# Sheet1.net
KiCad netlist of a schematic drawn in Altium Designer
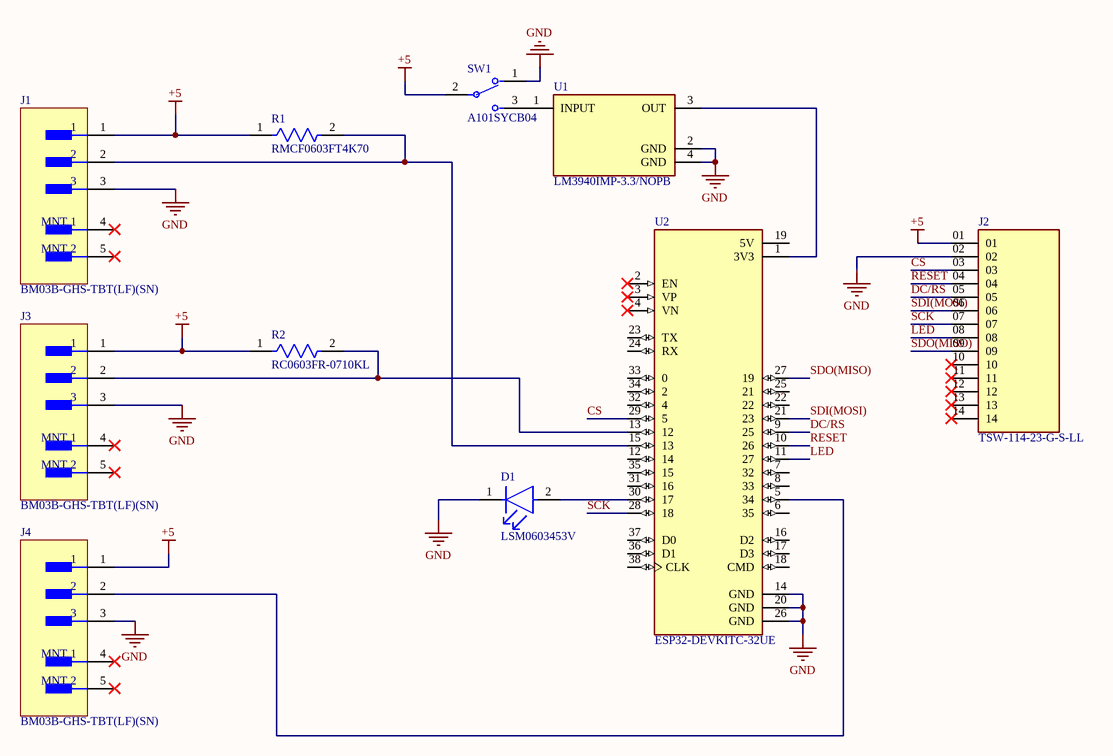
[diagram p0: Sheet1.SchDoc]

(export (version "E")
  (design (tool "Eeschema 10.0.6"))
  (components
    (comp (ref "D1")
      (value "LSM0603453V")
      (footprint "FP-LSM0603453V-MFG")
      (description "LSM0603453V LED SM 0603 3V -/1000/-mcd Green")
      (libsource (lib "Altium Content Vault") (part "8706943c75ba83719d021d2fdc84c58"))
    )
    (comp (ref "J1")
      (value "BM03B-GHS-TBT(LF)(SN)")
      (footprint "FP-BM03B-GHS-TBT_LF_SN-MFG")
      (description "CONN HEADER SMD 3POS 1.25MM")
      (libsource (lib "Altium Content Vault") (part "BM03B-GHS-TBT_LF_SN"))
    )
    (comp (ref "J2")
      (value "TSW-114-23-G-S-LL")
      (footprint "PcbLib1:SAMTEC_TSW-114-23-G-S-LL")
      (libsource (lib "Schlib1") (part "TSW-114-23-G-S-LL"))
    )
    (comp (ref "J3")
      (value "BM03B-GHS-TBT(LF)(SN)")
      (footprint "FP-BM03B-GHS-TBT_LF_SN-MFG")
      (description "CONN HEADER SMD 3POS 1.25MM")
      (libsource (lib "Altium Content Vault") (part "BM03B-GHS-TBT_LF_SN"))
    )
    (comp (ref "J4")
      (value "BM03B-GHS-TBT(LF)(SN)")
      (footprint "FP-BM03B-GHS-TBT_LF_SN-MFG")
      (description "CONN HEADER SMD 3POS 1.25MM")
      (libsource (lib "Altium Content Vault") (part "BM03B-GHS-TBT_LF_SN"))
    )
    (comp (ref "R1")
      (value "RMCF0603FT4K70")
      (footprint "FP-RMCF0603-IPC_B")
      (description "4.7kΩ ±1% 0.1W 0603 Thick Film Chip Resistor AEC-Q200 compliant")
      (fields (field (name "TOLERANCE") "1%"))
      (libsource (lib "Altium Content Vault") (part "1029c3af85768c4190bb7ad29bc67b5"))
    )
    (comp (ref "R2")
      (value "RC0603FR-0710KL")
      (footprint "FP-RC0603-0_55-IPC_C")
      (description "RES 10K OHM 1% 1/10W 0603")
      (fields (field (name "TOLERANCE") "1%"))
      (libsource (lib "Altium Content Vault") (part "1029c3af85768c4190bb7ad29bc67b5"))
    )
    (comp (ref "SW1")
      (value "A101SYCB04")
      (footprint "FP-A101SYCB04-MFG")
      (description "SWITCH TOGGLE SPDT 0.4VA 20V")
      (libsource (lib "Altium Content Vault") (part "52c419afdc2a387c7d548259a9aeefb"))
    )
    (comp (ref "U1")
      (value "LM3940IMP-3.3/NOPB")
      (footprint "FP-DCY0004A-MFG")
      (description "IC REG LINEAR 3.3V 1A SOT223-4")
      (libsource (lib "Altium Content Vault") (part "ef78896361455d16e3252a05c23564e"))
    )
    (comp (ref "U2")
      (value "ESP32-DEVKITC-32UE")
      (footprint "PcbLib1:ESPRESSIF_ESP32-DEVKITC-32UE")
      (fields (field (name "MF") "Espressif Systems"))
      (libsource (lib "Schlib1") (part "ESP32-DEVKITC-32UE"))
    )
  )
  (nets
    (net (code "1") (name "+5") (class "Default")
      (node (ref "J1") (pin "1") (pinfunction "1_1") (pintype "passive"))
      (node (ref "J2") (pin "01") (pinfunction "01_01") (pintype "passive"))
      (node (ref "J3") (pin "1") (pinfunction "1_1") (pintype "passive"))
      (node (ref "J4") (pin "1") (pinfunction "1_1") (pintype "passive"))
      (node (ref "R1") (pin "1") (pinfunction "1_1") (pintype "passive"))
      (node (ref "R2") (pin "1") (pinfunction "1_1") (pintype "passive"))
      (node (ref "SW1") (pin "2") (pinfunction "2_2") (pintype "passive"))
    )
    (net (code "2") (name "/CS") (class "Default")
      (node (ref "J2") (pin "03") (pinfunction "03_03") (pintype "passive"))
      (node (ref "U2") (pin "29") (pinfunction "5_29") (pintype "bidirectional"))
    )
    (net (code "3") (name "/DC{slash}RS") (class "Default")
      (node (ref "J2") (pin "05") (pinfunction "05_05") (pintype "passive"))
      (node (ref "U2") (pin "9") (pinfunction "25_9") (pintype "bidirectional"))
    )
    (net (code "4") (name "/LED") (class "Default")
      (node (ref "J2") (pin "08") (pinfunction "08_08") (pintype "passive"))
      (node (ref "U2") (pin "11") (pinfunction "27_11") (pintype "bidirectional"))
    )
    (net (code "5") (name "/RESET") (class "Default")
      (node (ref "J2") (pin "04") (pinfunction "04_04") (pintype "passive"))
      (node (ref "U2") (pin "10") (pinfunction "26_10") (pintype "bidirectional"))
    )
    (net (code "6") (name "/SCK") (class "Default")
      (node (ref "J2") (pin "07") (pinfunction "07_07") (pintype "passive"))
      (node (ref "U2") (pin "28") (pinfunction "18_28") (pintype "bidirectional"))
    )
    (net (code "7") (name "/SDI(MOSI)") (class "Default")
      (node (ref "J2") (pin "06") (pinfunction "06_06") (pintype "passive"))
      (node (ref "U2") (pin "21") (pinfunction "23_21") (pintype "bidirectional"))
    )
    (net (code "8") (name "/SDO(MISO)") (class "Default")
      (node (ref "J2") (pin "09") (pinfunction "09_09") (pintype "passive"))
      (node (ref "U2") (pin "27") (pinfunction "19_27") (pintype "bidirectional"))
    )
    (net (code "9") (name "GND") (class "Default")
      (node (ref "D1") (pin "1") (pinfunction "C_1") (pintype "passive"))
      (node (ref "J1") (pin "3") (pinfunction "3_3") (pintype "passive"))
      (node (ref "J2") (pin "02") (pinfunction "02_02") (pintype "passive"))
      (node (ref "J3") (pin "3") (pinfunction "3_3") (pintype "passive"))
      (node (ref "J4") (pin "3") (pinfunction "3_3") (pintype "passive"))
      (node (ref "SW1") (pin "1") (pinfunction "1_1") (pintype "passive"))
      (node (ref "U1") (pin "2") (pinfunction "GND_2") (pintype "power_in"))
      (node (ref "U1") (pin "4") (pinfunction "GND_4") (pintype "power_in"))
      (node (ref "U2") (pin "14") (pinfunction "GND_14") (pintype "power_in"))
      (node (ref "U2") (pin "20") (pinfunction "GND_20") (pintype "power_in"))
      (node (ref "U2") (pin "26") (pinfunction "GND_26") (pintype "power_in"))
    )
    (net (code "10") (name "Net-(D1-A)") (class "Default")
      (node (ref "D1") (pin "2") (pinfunction "A_2") (pintype "passive"))
      (node (ref "U2") (pin "30") (pinfunction "17_30") (pintype "bidirectional"))
    )
    (net (code "11") (name "Net-(U1-INPUT)") (class "Default")
      (node (ref "SW1") (pin "3") (pinfunction "3_3") (pintype "passive"))
      (node (ref "U1") (pin "1") (pinfunction "INPUT_1") (pintype "power_in"))
    )
    (net (code "12") (name "Net-(U1-OUT)") (class "Default")
      (node (ref "U1") (pin "3") (pinfunction "OUT_3") (pintype "power_in"))
      (node (ref "U2") (pin "1") (pinfunction "3V3_1") (pintype "power_in"))
    )
    (net (code "13") (name "Net-(U2-12)") (class "Default")
      (node (ref "J3") (pin "2") (pinfunction "2_2") (pintype "passive"))
      (node (ref "R2") (pin "2") (pinfunction "2_2") (pintype "passive"))
      (node (ref "U2") (pin "13") (pinfunction "12_13") (pintype "bidirectional"))
    )
    (net (code "14") (name "Net-(U2-13)") (class "Default")
      (node (ref "J1") (pin "2") (pinfunction "2_2") (pintype "passive"))
      (node (ref "R1") (pin "2") (pinfunction "2_2") (pintype "passive"))
      (node (ref "U2") (pin "15") (pinfunction "13_15") (pintype "bidirectional"))
    )
    (net (code "15") (name "Net-(U2-34)") (class "Default")
      (node (ref "J4") (pin "2") (pinfunction "2_2") (pintype "passive"))
      (node (ref "U2") (pin "5") (pinfunction "34_5") (pintype "bidirectional"))
    )
    (net (code "16") (name "unconnected-(J1-MNT_1-Pad4)") (class "Default")
      (node (ref "J1") (pin "4") (pinfunction "MNT_1_4") (pintype "passive+no_connect"))
    )
    (net (code "17") (name "unconnected-(J1-MNT_2-Pad5)") (class "Default")
      (node (ref "J1") (pin "5") (pinfunction "MNT_2_5") (pintype "passive+no_connect"))
    )
    (net (code "18") (name "unconnected-(J2-Pad10)") (class "Default")
      (node (ref "J2") (pin "10") (pinfunction "10_10") (pintype "passive+no_connect"))
    )
    (net (code "19") (name "unconnected-(J2-Pad11)") (class "Default")
      (node (ref "J2") (pin "11") (pinfunction "11_11") (pintype "passive+no_connect"))
    )
    (net (code "20") (name "unconnected-(J2-Pad12)") (class "Default")
      (node (ref "J2") (pin "12") (pinfunction "12_12") (pintype "passive+no_connect"))
    )
    (net (code "21") (name "unconnected-(J2-Pad13)") (class "Default")
      (node (ref "J2") (pin "13") (pinfunction "13_13") (pintype "passive+no_connect"))
    )
    (net (code "22") (name "unconnected-(J2-Pad14)") (class "Default")
      (node (ref "J2") (pin "14") (pinfunction "14_14") (pintype "passive+no_connect"))
    )
    (net (code "23") (name "unconnected-(J3-MNT_1-Pad4)") (class "Default")
      (node (ref "J3") (pin "4") (pinfunction "MNT_1_4") (pintype "passive+no_connect"))
    )
    (net (code "24") (name "unconnected-(J3-MNT_2-Pad5)") (class "Default")
      (node (ref "J3") (pin "5") (pinfunction "MNT_2_5") (pintype "passive+no_connect"))
    )
    (net (code "25") (name "unconnected-(J4-MNT_1-Pad4)") (class "Default")
      (node (ref "J4") (pin "4") (pinfunction "MNT_1_4") (pintype "passive+no_connect"))
    )
    (net (code "26") (name "unconnected-(J4-MNT_2-Pad5)") (class "Default")
      (node (ref "J4") (pin "5") (pinfunction "MNT_2_5") (pintype "passive+no_connect"))
    )
    (net (code "27") (name "unconnected-(U2-0-Pad33)") (class "Default")
      (node (ref "U2") (pin "33") (pinfunction "0_33") (pintype "bidirectional"))
    )
    (net (code "28") (name "unconnected-(U2-2-Pad34)") (class "Default")
      (node (ref "U2") (pin "34") (pinfunction "2_34") (pintype "bidirectional"))
    )
    (net (code "29") (name "unconnected-(U2-4-Pad32)") (class "Default")
      (node (ref "U2") (pin "32") (pinfunction "4_32") (pintype "bidirectional"))
    )
    (net (code "30") (name "unconnected-(U2-5V-Pad19)") (class "Default")
      (node (ref "U2") (pin "19") (pinfunction "5V_19") (pintype "power_in"))
    )
    (net (code "31") (name "unconnected-(U2-14-Pad12)") (class "Default")
      (node (ref "U2") (pin "12") (pinfunction "14_12") (pintype "bidirectional"))
    )
    (net (code "32") (name "unconnected-(U2-15-Pad35)") (class "Default")
      (node (ref "U2") (pin "35") (pinfunction "15_35") (pintype "bidirectional"))
    )
    (net (code "33") (name "unconnected-(U2-16-Pad31)") (class "Default")
      (node (ref "U2") (pin "31") (pinfunction "16_31") (pintype "bidirectional"))
    )
    (net (code "34") (name "unconnected-(U2-21-Pad25)") (class "Default")
      (node (ref "U2") (pin "25") (pinfunction "21_25") (pintype "bidirectional"))
    )
    (net (code "35") (name "unconnected-(U2-32-Pad7)") (class "Default")
      (node (ref "U2") (pin "7") (pinfunction "32_7") (pintype "bidirectional"))
    )
    (net (code "36") (name "unconnected-(U2-33-Pad8)") (class "Default")
      (node (ref "U2") (pin "8") (pinfunction "33_8") (pintype "bidirectional"))
    )
    (net (code "37") (name "unconnected-(U2-35-Pad6)") (class "Default")
      (node (ref "U2") (pin "6") (pinfunction "35_6") (pintype "bidirectional"))
    )
    (net (code "38") (name "unconnected-(U2-CLK-Pad38)") (class "Default")
      (node (ref "U2") (pin "38") (pinfunction "CLK_38") (pintype "bidirectional"))
    )
    (net (code "39") (name "unconnected-(U2-CMD-Pad18)") (class "Default")
      (node (ref "U2") (pin "18") (pinfunction "CMD_18") (pintype "bidirectional"))
    )
    (net (code "40") (name "unconnected-(U2-D0-Pad37)") (class "Default")
      (node (ref "U2") (pin "37") (pinfunction "D0_37") (pintype "bidirectional"))
    )
    (net (code "41") (name "unconnected-(U2-D1-Pad36)") (class "Default")
      (node (ref "U2") (pin "36") (pinfunction "D1_36") (pintype "bidirectional"))
    )
    (net (code "42") (name "unconnected-(U2-D2-Pad16)") (class "Default")
      (node (ref "U2") (pin "16") (pinfunction "D2_16") (pintype "bidirectional"))
    )
    (net (code "43") (name "unconnected-(U2-D3-Pad17)") (class "Default")
      (node (ref "U2") (pin "17") (pinfunction "D3_17") (pintype "bidirectional"))
    )
    (net (code "44") (name "unconnected-(U2-EN-Pad2)") (class "Default")
      (node (ref "U2") (pin "2") (pinfunction "EN_2") (pintype "input+no_connect"))
    )
    (net (code "45") (name "unconnected-(U2-Pad22)") (class "Default")
      (node (ref "U2") (pin "22") (pinfunction "22_22") (pintype "bidirectional"))
    )
    (net (code "46") (name "unconnected-(U2-RX-Pad24)") (class "Default")
      (node (ref "U2") (pin "24") (pinfunction "RX_24") (pintype "bidirectional"))
    )
    (net (code "47") (name "unconnected-(U2-TX-Pad23)") (class "Default")
      (node (ref "U2") (pin "23") (pinfunction "TX_23") (pintype "bidirectional"))
    )
    (net (code "48") (name "unconnected-(U2-VN-Pad4)") (class "Default")
      (node (ref "U2") (pin "4") (pinfunction "VN_4") (pintype "input+no_connect"))
    )
    (net (code "49") (name "unconnected-(U2-VP-Pad3)") (class "Default")
      (node (ref "U2") (pin "3") (pinfunction "VP_3") (pintype "input+no_connect"))
    )
  )
)
